# HDA-v1_1.net
KiCad netlist of a schematic drawn in EAGLE
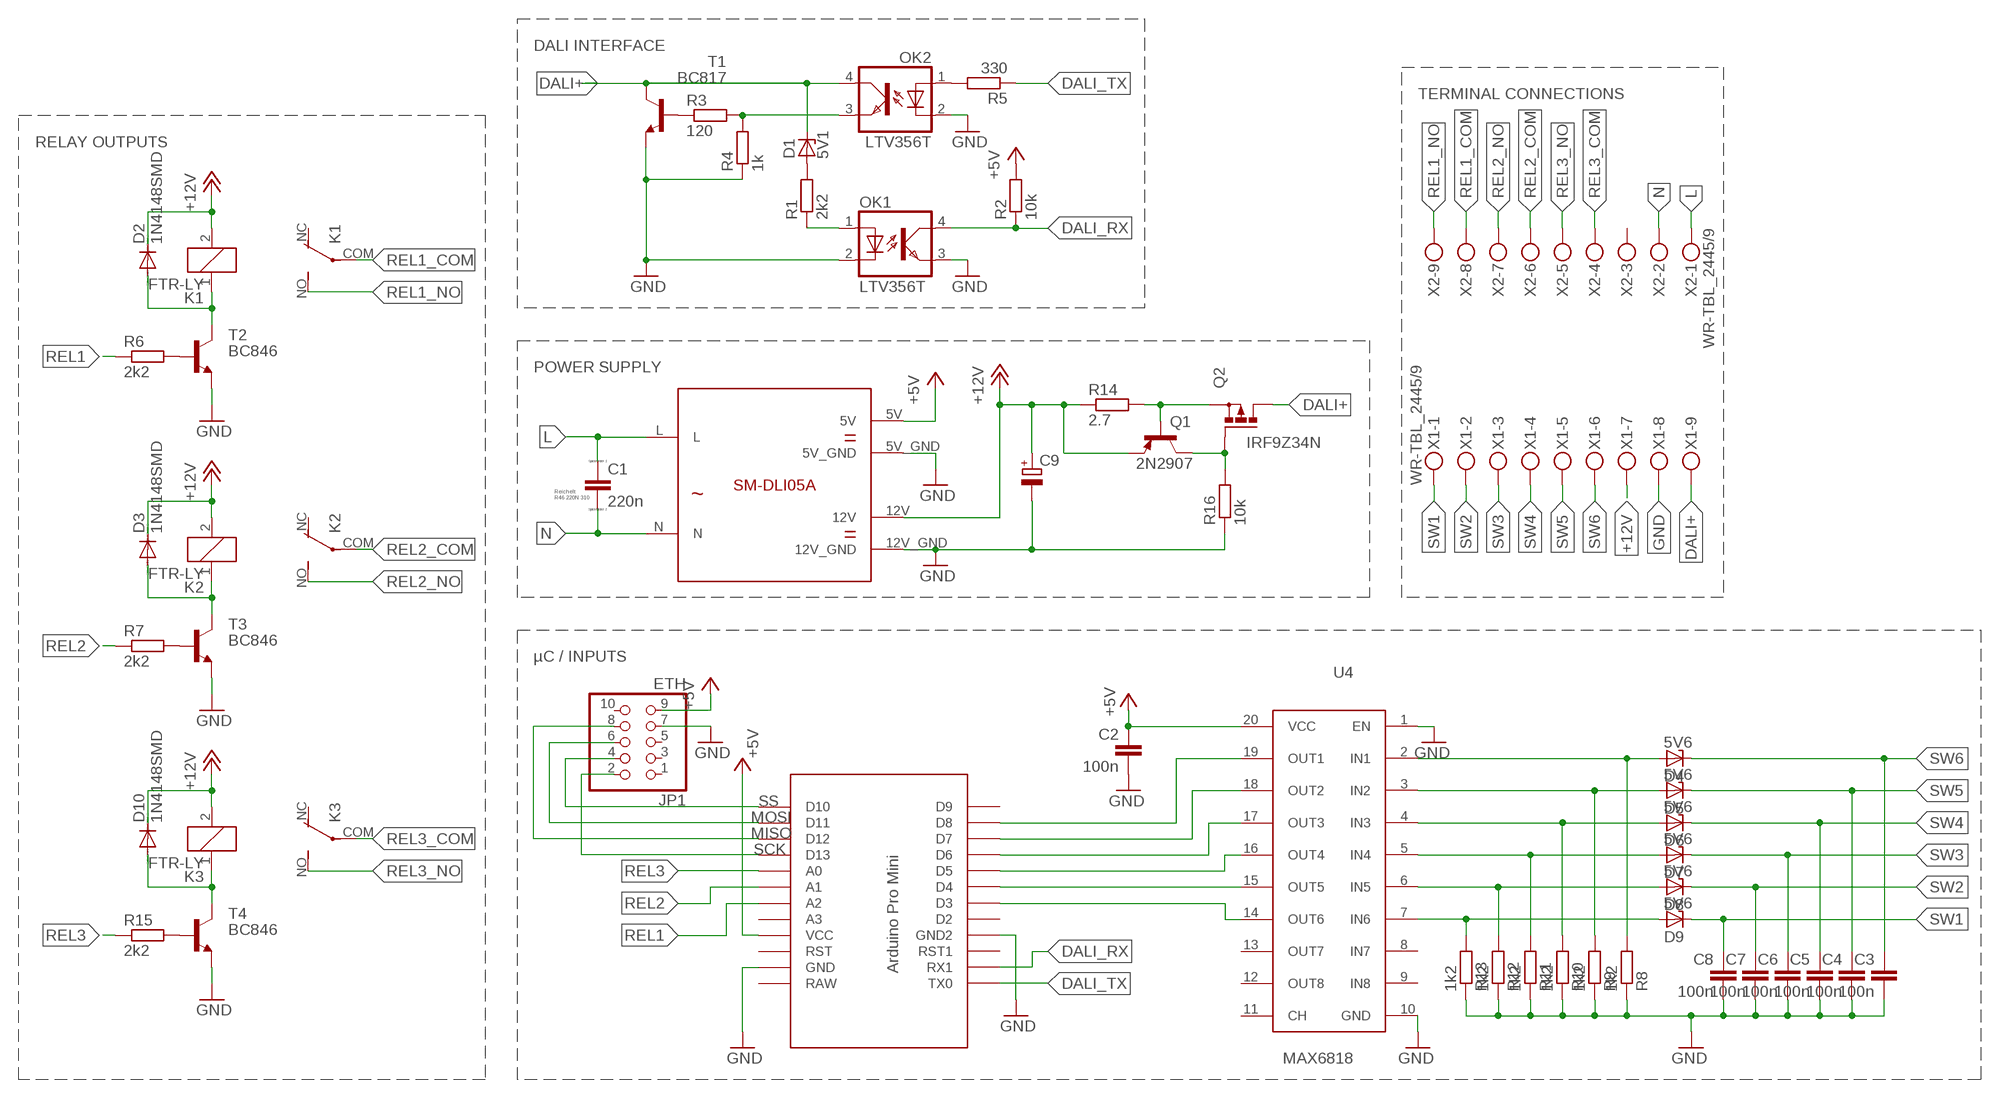
[diagram p0: schematic, sheet 1]

(export (version "E")
  (design (tool "Eeschema 10.0.6"))
  (components
    (comp (ref "C1")
      (value "220n")
      (footprint "eagle-import:ECQUAAF224")
      (libsource (lib "eagle-import") (part "X2_220N"))
    )
    (comp (ref "C2")
      (value "100n")
      (footprint "eagle-import:C1206K")
      (libsource (lib "eagle-import") (part "C-EUC1206K"))
    )
    (comp (ref "C3")
      (value "100n")
      (footprint "eagle-import:C1206K")
      (libsource (lib "eagle-import") (part "C-EUC1206K"))
    )
    (comp (ref "C4")
      (value "100n")
      (footprint "eagle-import:C1206K")
      (libsource (lib "eagle-import") (part "C-EUC1206K"))
    )
    (comp (ref "C5")
      (value "100n")
      (footprint "eagle-import:C1206K")
      (libsource (lib "eagle-import") (part "C-EUC1206K"))
    )
    (comp (ref "C6")
      (value "100n")
      (footprint "eagle-import:C1206K")
      (libsource (lib "eagle-import") (part "C-EUC1206K"))
    )
    (comp (ref "C7")
      (value "100n")
      (footprint "eagle-import:C1206K")
      (libsource (lib "eagle-import") (part "C-EUC1206K"))
    )
    (comp (ref "C8")
      (value "100n")
      (footprint "eagle-import:C1206K")
      (libsource (lib "eagle-import") (part "C-EUC1206K"))
    )
    (comp (ref "C9")
      (value "CPOL-EUSMCE")
      (footprint "eagle-import:SMC_E")
      (libsource (lib "eagle-import") (part "CPOL-EUSMCE"))
    )
    (comp (ref "D1")
      (value "5V1")
      (footprint "eagle-import:SOD80C")
      (libsource (lib "eagle-import") (part "ZENER-DIODESOD80C"))
    )
    (comp (ref "D2")
      (value "1N4148SMD")
      (footprint "eagle-import:SOD80C")
      (libsource (lib "eagle-import") (part "DIODE-SOD80C"))
    )
    (comp (ref "D3")
      (value "1N4148SMD")
      (footprint "eagle-import:SOD80C")
      (libsource (lib "eagle-import") (part "DIODE-SOD80C"))
    )
    (comp (ref "D4")
      (value "5V6")
      (footprint "eagle-import:SOD80C")
      (libsource (lib "eagle-import") (part "ZENER-DIODESOD80C"))
    )
    (comp (ref "D5")
      (value "5V6")
      (footprint "eagle-import:SOD80C")
      (libsource (lib "eagle-import") (part "ZENER-DIODESOD80C"))
    )
    (comp (ref "D6")
      (value "5V6")
      (footprint "eagle-import:SOD80C")
      (libsource (lib "eagle-import") (part "ZENER-DIODESOD80C"))
    )
    (comp (ref "D7")
      (value "5V6")
      (footprint "eagle-import:SOD80C")
      (libsource (lib "eagle-import") (part "ZENER-DIODESOD80C"))
    )
    (comp (ref "D8")
      (value "5V6")
      (footprint "eagle-import:SOD80C")
      (libsource (lib "eagle-import") (part "ZENER-DIODESOD80C"))
    )
    (comp (ref "D9")
      (value "5V6")
      (footprint "eagle-import:SOD80C")
      (libsource (lib "eagle-import") (part "ZENER-DIODESOD80C"))
    )
    (comp (ref "D10")
      (value "1N4148SMD")
      (footprint "eagle-import:SOD80C")
      (libsource (lib "eagle-import") (part "DIODE-SOD80C"))
    )
    (comp (ref "JP1")
      (value "ETH")
      (footprint "eagle-import:2X05")
      (libsource (lib "eagle-import") (part "PINHD-2X5"))
    )
    (comp (ref "K1")
      (value "FTR-LY")
      (footprint "eagle-import:PE-FORM-C")
      (fields (field (name "MPN") "APE3004H"))
      (libsource (lib "eagle-import") (part "PE30?04H"))
    )
    (comp (ref "K2")
      (value "FTR-LY")
      (footprint "eagle-import:PE-FORM-C")
      (fields (field (name "MPN") "APE3004H"))
      (libsource (lib "eagle-import") (part "PE30?04H"))
    )
    (comp (ref "K3")
      (value "FTR-LY")
      (footprint "eagle-import:PE-FORM-C")
      (fields (field (name "MPN") "APE3004H"))
      (libsource (lib "eagle-import") (part "PE30?04H"))
    )
    (comp (ref "OK1")
      (value "LTV356T")
      (footprint "eagle-import:SOP-4-2.54")
      (libsource (lib "eagle-import") (part "LTV356T"))
    )
    (comp (ref "OK2")
      (value "LTV356T")
      (footprint "eagle-import:SOP-4-2.54")
      (libsource (lib "eagle-import") (part "LTV356T"))
    )
    (comp (ref "Q1")
      (value "2N2907")
      (footprint "eagle-import:SOT23-BEC")
      (libsource (lib "eagle-import") (part "MMBT2907SMDALT1"))
    )
    (comp (ref "Q2")
      (value "IRF9Z34N")
      (footprint "eagle-import:TO220BV")
      (libsource (lib "eagle-import") (part "PMOSFET_PTO220BV"))
    )
    (comp (ref "R1")
      (value "2k2")
      (footprint "eagle-import:R1206")
      (libsource (lib "eagle-import") (part "R-EU_R1206"))
    )
    (comp (ref "R2")
      (value "10k")
      (footprint "eagle-import:R1206")
      (libsource (lib "eagle-import") (part "R-EU_R1206"))
    )
    (comp (ref "R3")
      (value "120")
      (footprint "eagle-import:R1206")
      (libsource (lib "eagle-import") (part "R-EU_R1206"))
    )
    (comp (ref "R4")
      (value "1k")
      (footprint "eagle-import:R1206")
      (libsource (lib "eagle-import") (part "R-EU_R1206"))
    )
    (comp (ref "R5")
      (value "330")
      (footprint "eagle-import:R1206")
      (libsource (lib "eagle-import") (part "R-EU_R1206"))
    )
    (comp (ref "R6")
      (value "2k2")
      (footprint "eagle-import:R1206")
      (libsource (lib "eagle-import") (part "R-EU_R1206"))
    )
    (comp (ref "R7")
      (value "2k2")
      (footprint "eagle-import:R1206")
      (libsource (lib "eagle-import") (part "R-EU_R1206"))
    )
    (comp (ref "R8")
      (value "1k2")
      (footprint "eagle-import:R1206")
      (libsource (lib "eagle-import") (part "R-EU_R1206"))
    )
    (comp (ref "R9")
      (value "1k2")
      (footprint "eagle-import:R1206")
      (libsource (lib "eagle-import") (part "R-EU_R1206"))
    )
    (comp (ref "R10")
      (value "1k2")
      (footprint "eagle-import:R1206")
      (libsource (lib "eagle-import") (part "R-EU_R1206"))
    )
    (comp (ref "R11")
      (value "1k2")
      (footprint "eagle-import:R1206")
      (libsource (lib "eagle-import") (part "R-EU_R1206"))
    )
    (comp (ref "R12")
      (value "1k2")
      (footprint "eagle-import:R1206")
      (libsource (lib "eagle-import") (part "R-EU_R1206"))
    )
    (comp (ref "R13")
      (value "1k2")
      (footprint "eagle-import:R1206")
      (libsource (lib "eagle-import") (part "R-EU_R1206"))
    )
    (comp (ref "R14")
      (value "2.7")
      (footprint "eagle-import:R1206")
      (libsource (lib "eagle-import") (part "R-EU_R1206"))
    )
    (comp (ref "R15")
      (value "2k2")
      (footprint "eagle-import:R1206")
      (libsource (lib "eagle-import") (part "R-EU_R1206"))
    )
    (comp (ref "R16")
      (value "10k")
      (footprint "eagle-import:R1206")
      (libsource (lib "eagle-import") (part "R-EU_R1206"))
    )
    (comp (ref "T1")
      (value "BC817")
      (footprint "eagle-import:SOT23-BEC")
      (libsource (lib "eagle-import") (part "BC817SMD-40"))
    )
    (comp (ref "T2")
      (value "BC846")
      (footprint "eagle-import:SOT23")
      (libsource (lib "eagle-import") (part "BC846"))
    )
    (comp (ref "T3")
      (value "BC846")
      (footprint "eagle-import:SOT23")
      (libsource (lib "eagle-import") (part "BC846"))
    )
    (comp (ref "T4")
      (value "BC846")
      (footprint "eagle-import:SOT23")
      (libsource (lib "eagle-import") (part "BC846"))
    )
    (comp (ref "U1")
      (value "SM-DLI05A")
      (footprint "eagle-import:SM-DLI05A")
      (libsource (lib "eagle-import") (part "SM-DLI05A"))
    )
    (comp (ref "U2")
      (value "ABK-PRO-MINI")
      (footprint "eagle-import:ABK-PRO-MINI")
      (libsource (lib "eagle-import") (part "ABK-PRO-MINI"))
    )
    (comp (ref "U4")
      (value "MAX6818")
      (footprint "eagle-import:SSOP20")
      (libsource (lib "eagle-import") (part "MAX6818"))
    )
    (comp (ref "X1")
      (value "WR-TBL_2445/9")
      (footprint "eagle-import:WR-TBL_2445_9")
      (libsource (lib "eagle-import") (part "WR-TBL_2445/9"))
    )
    (comp (ref "X2")
      (value "WR-TBL_2445/9")
      (footprint "eagle-import:WR-TBL_2445_9")
      (libsource (lib "eagle-import") (part "WR-TBL_2445/9"))
    )
  )
  (nets
    (net (code "1") (name "+5V") (class "Default")
      (node (ref "C2") (pin "1") (pinfunction "1_1") (pintype "passive"))
      (node (ref "JP1") (pin "9") (pinfunction "9_9") (pintype "passive"))
      (node (ref "R2") (pin "2") (pinfunction "2_2") (pintype "passive"))
      (node (ref "U1") (pin "5V") (pinfunction "5V_5V") (pintype "bidirectional"))
      (node (ref "U2") (pin "VCC") (pinfunction "VCC_VCC") (pintype "bidirectional"))
      (node (ref "U4") (pin "20") (pinfunction "VCC_20") (pintype "power_in"))
    )
    (net (code "2") (name "+12V") (class "Default")
      (node (ref "C9") (pin "+") (pinfunction "+_+") (pintype "passive"))
      (node (ref "D10") (pin "C") (pinfunction "C_C") (pintype "passive"))
      (node (ref "D2") (pin "C") (pinfunction "C_C") (pintype "passive"))
      (node (ref "D3") (pin "C") (pinfunction "C_C") (pintype "passive"))
      (node (ref "K1") (pin "2") (pinfunction "2_2") (pintype "passive"))
      (node (ref "K2") (pin "2") (pinfunction "2_2") (pintype "passive"))
      (node (ref "K3") (pin "2") (pinfunction "2_2") (pintype "passive"))
      (node (ref "Q1") (pin "E") (pinfunction "E_E") (pintype "passive"))
      (node (ref "R14") (pin "1") (pinfunction "1_1") (pintype "passive"))
      (node (ref "U1") (pin "12V") (pinfunction "12V_12V") (pintype "bidirectional"))
      (node (ref "X1") (pin "7") (pinfunction "KL_7") (pintype "passive"))
    )
    (net (code "3") (name "/MISO") (class "Default")
      (node (ref "JP1") (pin "8") (pinfunction "8_8") (pintype "passive"))
      (node (ref "U2") (pin "D12") (pinfunction "D12_D12") (pintype "bidirectional"))
    )
    (net (code "4") (name "/MOSI") (class "Default")
      (node (ref "JP1") (pin "6") (pinfunction "6_6") (pintype "passive"))
      (node (ref "U2") (pin "D11") (pinfunction "D11_D11") (pintype "bidirectional"))
    )
    (net (code "5") (name "/SCK") (class "Default")
      (node (ref "JP1") (pin "2") (pinfunction "2_2") (pintype "passive"))
      (node (ref "U2") (pin "D13") (pinfunction "D13_D13") (pintype "bidirectional"))
    )
    (net (code "6") (name "/SS") (class "Default")
      (node (ref "JP1") (pin "4") (pinfunction "4_4") (pintype "passive"))
      (node (ref "U2") (pin "D10") (pinfunction "D10_D10") (pintype "bidirectional"))
    )
    (net (code "7") (name "DALI+") (class "Default")
      (node (ref "D1") (pin "C") (pinfunction "C_C") (pintype "passive"))
      (node (ref "OK2") (pin "4") (pinfunction "COL_4") (pintype "passive"))
      (node (ref "Q2") (pin "D") (pinfunction "D_D") (pintype "passive"))
      (node (ref "T1") (pin "C") (pinfunction "C_C") (pintype "passive"))
      (node (ref "X1") (pin "9") (pinfunction "KL_9") (pintype "passive"))
    )
    (net (code "8") (name "DALI_RX") (class "Default")
      (node (ref "OK1") (pin "4") (pinfunction "COL_4") (pintype "passive"))
      (node (ref "R2") (pin "1") (pinfunction "1_1") (pintype "passive"))
      (node (ref "U2") (pin "RX1") (pinfunction "RX1_RX1") (pintype "bidirectional"))
    )
    (net (code "9") (name "DALI_TX") (class "Default")
      (node (ref "R5") (pin "1") (pinfunction "1_1") (pintype "passive"))
      (node (ref "U2") (pin "TX0") (pinfunction "TX0_TX0") (pintype "bidirectional"))
    )
    (net (code "10") (name "GND") (class "Default")
      (node (ref "C2") (pin "2") (pinfunction "2_2") (pintype "passive"))
      (node (ref "C3") (pin "2") (pinfunction "2_2") (pintype "passive"))
      (node (ref "C4") (pin "2") (pinfunction "2_2") (pintype "passive"))
      (node (ref "C5") (pin "2") (pinfunction "2_2") (pintype "passive"))
      (node (ref "C6") (pin "2") (pinfunction "2_2") (pintype "passive"))
      (node (ref "C7") (pin "2") (pinfunction "2_2") (pintype "passive"))
      (node (ref "C8") (pin "2") (pinfunction "2_2") (pintype "passive"))
      (node (ref "C9") (pin "-") (pinfunction "-_-") (pintype "passive"))
      (node (ref "JP1") (pin "7") (pinfunction "7_7") (pintype "passive"))
      (node (ref "OK1") (pin "2") (pinfunction "C_2") (pintype "passive"))
      (node (ref "OK1") (pin "3") (pinfunction "EMIT_3") (pintype "passive"))
      (node (ref "OK2") (pin "2") (pinfunction "C_2") (pintype "passive"))
      (node (ref "R10") (pin "1") (pinfunction "1_1") (pintype "passive"))
      (node (ref "R11") (pin "1") (pinfunction "1_1") (pintype "passive"))
      (node (ref "R12") (pin "1") (pinfunction "1_1") (pintype "passive"))
      (node (ref "R13") (pin "1") (pinfunction "1_1") (pintype "passive"))
      (node (ref "R16") (pin "1") (pinfunction "1_1") (pintype "passive"))
      (node (ref "R4") (pin "1") (pinfunction "1_1") (pintype "passive"))
      (node (ref "R8") (pin "1") (pinfunction "1_1") (pintype "passive"))
      (node (ref "R9") (pin "1") (pinfunction "1_1") (pintype "passive"))
      (node (ref "T1") (pin "E") (pinfunction "E_E") (pintype "passive"))
      (node (ref "T2") (pin "2") (pinfunction "E_2") (pintype "passive"))
      (node (ref "T3") (pin "2") (pinfunction "E_2") (pintype "passive"))
      (node (ref "T4") (pin "2") (pinfunction "E_2") (pintype "passive"))
      (node (ref "U1") (pin "12V_GND") (pinfunction "12V_GND_12V_GND") (pintype "bidirectional"))
      (node (ref "U1") (pin "5V_GND") (pinfunction "5V_GND_5V_GND") (pintype "bidirectional"))
      (node (ref "U2") (pin "GND") (pinfunction "GND_GND") (pintype "bidirectional"))
      (node (ref "U2") (pin "GND1") (pinfunction "GND2_GND1") (pintype "bidirectional"))
      (node (ref "U4") (pin "1") (pinfunction "EN_1") (pintype "bidirectional"))
      (node (ref "U4") (pin "10") (pinfunction "GND_10") (pintype "power_in"))
      (node (ref "X1") (pin "8") (pinfunction "KL_8") (pintype "passive"))
    )
    (net (code "11") (name "L") (class "Default")
      (node (ref "C1") (pin "1") (pinfunction "1_1") (pintype "passive"))
      (node (ref "U1") (pin "L") (pinfunction "L_L") (pintype "bidirectional"))
      (node (ref "X2") (pin "1") (pinfunction "KL_1") (pintype "passive"))
    )
    (net (code "12") (name "N") (class "Default")
      (node (ref "C1") (pin "2") (pinfunction "2_2") (pintype "passive"))
      (node (ref "U1") (pin "N") (pinfunction "N_N") (pintype "bidirectional"))
      (node (ref "X2") (pin "2") (pinfunction "KL_2") (pintype "passive"))
    )
    (net (code "13") (name "Net-(D1-PadA)") (class "Default")
      (node (ref "D1") (pin "A") (pinfunction "A_A") (pintype "passive"))
      (node (ref "R1") (pin "2") (pinfunction "2_2") (pintype "passive"))
    )
    (net (code "14") (name "Net-(OK1-A)") (class "Default")
      (node (ref "OK1") (pin "1") (pinfunction "A_1") (pintype "passive"))
      (node (ref "R1") (pin "1") (pinfunction "1_1") (pintype "passive"))
    )
    (net (code "15") (name "Net-(OK2-A)") (class "Default")
      (node (ref "OK2") (pin "1") (pinfunction "A_1") (pintype "passive"))
      (node (ref "R5") (pin "2") (pinfunction "2_2") (pintype "passive"))
    )
    (net (code "16") (name "Net-(OK2-EMIT)") (class "Default")
      (node (ref "OK2") (pin "3") (pinfunction "EMIT_3") (pintype "passive"))
      (node (ref "R3") (pin "2") (pinfunction "2_2") (pintype "passive"))
      (node (ref "R4") (pin "2") (pinfunction "2_2") (pintype "passive"))
    )
    (net (code "17") (name "Net-(Q1-PadB)") (class "Default")
      (node (ref "Q1") (pin "B") (pinfunction "B_B") (pintype "passive"))
      (node (ref "Q2") (pin "S") (pinfunction "S_S") (pintype "passive"))
      (node (ref "R14") (pin "2") (pinfunction "2_2") (pintype "passive"))
    )
    (net (code "18") (name "Net-(Q1-PadC)") (class "Default")
      (node (ref "Q1") (pin "C") (pinfunction "C_C") (pintype "passive"))
      (node (ref "Q2") (pin "G") (pinfunction "G_G") (pintype "passive"))
      (node (ref "R16") (pin "2") (pinfunction "2_2") (pintype "passive"))
    )
    (net (code "19") (name "Net-(R3-Pad1)") (class "Default")
      (node (ref "R3") (pin "1") (pinfunction "1_1") (pintype "passive"))
      (node (ref "T1") (pin "B") (pinfunction "B_B") (pintype "passive"))
    )
    (net (code "20") (name "Net-(T2-B)") (class "Default")
      (node (ref "R6") (pin "2") (pinfunction "2_2") (pintype "passive"))
      (node (ref "T2") (pin "1") (pinfunction "B_1") (pintype "passive"))
    )
    (net (code "21") (name "Net-(T2-C)") (class "Default")
      (node (ref "D2") (pin "A") (pinfunction "A_A") (pintype "passive"))
      (node (ref "K1") (pin "1") (pinfunction "1_1") (pintype "passive"))
      (node (ref "T2") (pin "3") (pinfunction "C_3") (pintype "passive"))
    )
    (net (code "22") (name "Net-(T3-B)") (class "Default")
      (node (ref "R7") (pin "2") (pinfunction "2_2") (pintype "passive"))
      (node (ref "T3") (pin "1") (pinfunction "B_1") (pintype "passive"))
    )
    (net (code "23") (name "Net-(T3-C)") (class "Default")
      (node (ref "D3") (pin "A") (pinfunction "A_A") (pintype "passive"))
      (node (ref "K2") (pin "1") (pinfunction "1_1") (pintype "passive"))
      (node (ref "T3") (pin "3") (pinfunction "C_3") (pintype "passive"))
    )
    (net (code "24") (name "Net-(T4-B)") (class "Default")
      (node (ref "R15") (pin "2") (pinfunction "2_2") (pintype "passive"))
      (node (ref "T4") (pin "1") (pinfunction "B_1") (pintype "passive"))
    )
    (net (code "25") (name "Net-(T4-C)") (class "Default")
      (node (ref "D10") (pin "A") (pinfunction "A_A") (pintype "passive"))
      (node (ref "K3") (pin "1") (pinfunction "1_1") (pintype "passive"))
      (node (ref "T4") (pin "3") (pinfunction "C_3") (pintype "passive"))
    )
    (net (code "26") (name "Net-(U4-IN1)") (class "Default")
      (node (ref "D4") (pin "A") (pinfunction "A_A") (pintype "passive"))
      (node (ref "R8") (pin "2") (pinfunction "2_2") (pintype "passive"))
      (node (ref "U4") (pin "2") (pinfunction "IN1_2") (pintype "bidirectional"))
    )
    (net (code "27") (name "Net-(U4-IN2)") (class "Default")
      (node (ref "D5") (pin "A") (pinfunction "A_A") (pintype "passive"))
      (node (ref "R9") (pin "2") (pinfunction "2_2") (pintype "passive"))
      (node (ref "U4") (pin "3") (pinfunction "IN2_3") (pintype "bidirectional"))
    )
    (net (code "28") (name "Net-(U4-IN3)") (class "Default")
      (node (ref "D6") (pin "A") (pinfunction "A_A") (pintype "passive"))
      (node (ref "R10") (pin "2") (pinfunction "2_2") (pintype "passive"))
      (node (ref "U4") (pin "4") (pinfunction "IN3_4") (pintype "bidirectional"))
    )
    (net (code "29") (name "Net-(U4-IN4)") (class "Default")
      (node (ref "D7") (pin "A") (pinfunction "A_A") (pintype "passive"))
      (node (ref "R11") (pin "2") (pinfunction "2_2") (pintype "passive"))
      (node (ref "U4") (pin "5") (pinfunction "IN4_5") (pintype "bidirectional"))
    )
    (net (code "30") (name "Net-(U4-IN5)") (class "Default")
      (node (ref "D8") (pin "A") (pinfunction "A_A") (pintype "passive"))
      (node (ref "R12") (pin "2") (pinfunction "2_2") (pintype "passive"))
      (node (ref "U4") (pin "6") (pinfunction "IN5_6") (pintype "bidirectional"))
    )
    (net (code "31") (name "Net-(U4-IN6)") (class "Default")
      (node (ref "D9") (pin "A") (pinfunction "A_A") (pintype "passive"))
      (node (ref "R13") (pin "2") (pinfunction "2_2") (pintype "passive"))
      (node (ref "U4") (pin "7") (pinfunction "IN6_7") (pintype "bidirectional"))
    )
    (net (code "32") (name "Net-(U4-OUT1)") (class "Default")
      (node (ref "U2") (pin "D8") (pinfunction "D8_D8") (pintype "bidirectional"))
      (node (ref "U4") (pin "19") (pinfunction "OUT1_19") (pintype "bidirectional"))
    )
    (net (code "33") (name "Net-(U4-OUT2)") (class "Default")
      (node (ref "U2") (pin "D7") (pinfunction "D7_D7") (pintype "bidirectional"))
      (node (ref "U4") (pin "18") (pinfunction "OUT2_18") (pintype "bidirectional"))
    )
    (net (code "34") (name "Net-(U4-OUT3)") (class "Default")
      (node (ref "U2") (pin "D6") (pinfunction "D6_D6") (pintype "bidirectional"))
      (node (ref "U4") (pin "17") (pinfunction "OUT3_17") (pintype "bidirectional"))
    )
    (net (code "35") (name "Net-(U4-OUT4)") (class "Default")
      (node (ref "U2") (pin "D5") (pinfunction "D5_D5") (pintype "bidirectional"))
      (node (ref "U4") (pin "16") (pinfunction "OUT4_16") (pintype "bidirectional"))
    )
    (net (code "36") (name "Net-(U4-OUT5)") (class "Default")
      (node (ref "U2") (pin "D4") (pinfunction "D4_D4") (pintype "bidirectional"))
      (node (ref "U4") (pin "15") (pinfunction "OUT5_15") (pintype "bidirectional"))
    )
    (net (code "37") (name "Net-(U4-OUT6)") (class "Default")
      (node (ref "U2") (pin "D3") (pinfunction "D3_D3") (pintype "bidirectional"))
      (node (ref "U4") (pin "14") (pinfunction "OUT6_14") (pintype "bidirectional"))
    )
    (net (code "38") (name "REL1") (class "Default")
      (node (ref "R6") (pin "1") (pinfunction "1_1") (pintype "passive"))
      (node (ref "U2") (pin "A2") (pinfunction "A2_A2") (pintype "bidirectional"))
    )
    (net (code "39") (name "REL1_COM") (class "Default")
      (node (ref "K1") (pin "COM") (pinfunction "P_COM") (pintype "passive"))
      (node (ref "X2") (pin "8") (pinfunction "KL_8") (pintype "passive"))
    )
    (net (code "40") (name "REL1_NO") (class "Default")
      (node (ref "K1") (pin "NO") (pinfunction "S_NO") (pintype "passive"))
      (node (ref "X2") (pin "9") (pinfunction "KL_9") (pintype "passive"))
    )
    (net (code "41") (name "REL2") (class "Default")
      (node (ref "R7") (pin "1") (pinfunction "1_1") (pintype "passive"))
      (node (ref "U2") (pin "A1") (pinfunction "A1_A1") (pintype "bidirectional"))
    )
    (net (code "42") (name "REL2_COM") (class "Default")
      (node (ref "K2") (pin "COM") (pinfunction "P_COM") (pintype "passive"))
      (node (ref "X2") (pin "6") (pinfunction "KL_6") (pintype "passive"))
    )
    (net (code "43") (name "REL2_NO") (class "Default")
      (node (ref "K2") (pin "NO") (pinfunction "S_NO") (pintype "passive"))
      (node (ref "X2") (pin "7") (pinfunction "KL_7") (pintype "passive"))
    )
    (net (code "44") (name "REL3") (class "Default")
      (node (ref "R15") (pin "1") (pinfunction "1_1") (pintype "passive"))
      (node (ref "U2") (pin "A0") (pinfunction "A0_A0") (pintype "bidirectional"))
    )
    (net (code "45") (name "REL3_COM") (class "Default")
      (node (ref "K3") (pin "COM") (pinfunction "P_COM") (pintype "passive"))
      (node (ref "X2") (pin "4") (pinfunction "KL_4") (pintype "passive"))
    )
    (net (code "46") (name "REL3_NO") (class "Default")
      (node (ref "K3") (pin "NO") (pinfunction "S_NO") (pintype "passive"))
      (node (ref "X2") (pin "5") (pinfunction "KL_5") (pintype "passive"))
    )
    (net (code "47") (name "SW1") (class "Default")
      (node (ref "C8") (pin "1") (pinfunction "1_1") (pintype "passive"))
      (node (ref "D9") (pin "C") (pinfunction "C_C") (pintype "passive"))
      (node (ref "X1") (pin "1") (pinfunction "KL_1") (pintype "passive"))
    )
    (net (code "48") (name "SW2") (class "Default")
      (node (ref "C7") (pin "1") (pinfunction "1_1") (pintype "passive"))
      (node (ref "D8") (pin "C") (pinfunction "C_C") (pintype "passive"))
      (node (ref "X1") (pin "2") (pinfunction "KL_2") (pintype "passive"))
    )
    (net (code "49") (name "SW3") (class "Default")
      (node (ref "C6") (pin "1") (pinfunction "1_1") (pintype "passive"))
      (node (ref "D7") (pin "C") (pinfunction "C_C") (pintype "passive"))
      (node (ref "X1") (pin "3") (pinfunction "KL_3") (pintype "passive"))
    )
    (net (code "50") (name "SW4") (class "Default")
      (node (ref "C5") (pin "1") (pinfunction "1_1") (pintype "passive"))
      (node (ref "D6") (pin "C") (pinfunction "C_C") (pintype "passive"))
      (node (ref "X1") (pin "4") (pinfunction "KL_4") (pintype "passive"))
    )
    (net (code "51") (name "SW5") (class "Default")
      (node (ref "C4") (pin "1") (pinfunction "1_1") (pintype "passive"))
      (node (ref "D5") (pin "C") (pinfunction "C_C") (pintype "passive"))
      (node (ref "X1") (pin "5") (pinfunction "KL_5") (pintype "passive"))
    )
    (net (code "52") (name "SW6") (class "Default")
      (node (ref "C3") (pin "1") (pinfunction "1_1") (pintype "passive"))
      (node (ref "D4") (pin "C") (pinfunction "C_C") (pintype "passive"))
      (node (ref "X1") (pin "6") (pinfunction "KL_6") (pintype "passive"))
    )
    (net (code "53") (name "unconnected-(JP1-Pad1)") (class "Default")
      (node (ref "JP1") (pin "1") (pinfunction "1_1") (pintype "passive"))
    )
    (net (code "54") (name "unconnected-(JP1-Pad3)") (class "Default")
      (node (ref "JP1") (pin "3") (pinfunction "3_3") (pintype "passive"))
    )
    (net (code "55") (name "unconnected-(JP1-Pad5)") (class "Default")
      (node (ref "JP1") (pin "5") (pinfunction "5_5") (pintype "passive"))
    )
    (net (code "56") (name "unconnected-(JP1-Pad10)") (class "Default")
      (node (ref "JP1") (pin "10") (pinfunction "10_10") (pintype "passive"))
    )
    (net (code "57") (name "unconnected-(K1B-O-PadNC)") (class "Default")
      (node (ref "K1") (pin "NC") (pinfunction "O_NC") (pintype "passive"))
    )
    (net (code "58") (name "unconnected-(K2B-O-PadNC)") (class "Default")
      (node (ref "K2") (pin "NC") (pinfunction "O_NC") (pintype "passive"))
    )
    (net (code "59") (name "unconnected-(K3B-O-PadNC)") (class "Default")
      (node (ref "K3") (pin "NC") (pinfunction "O_NC") (pintype "passive"))
    )
    (net (code "60") (name "unconnected-(U2-PadA3)") (class "Default")
      (node (ref "U2") (pin "A3") (pinfunction "A3_A3") (pintype "bidirectional"))
    )
    (net (code "61") (name "unconnected-(U2-PadD2)") (class "Default")
      (node (ref "U2") (pin "D2") (pinfunction "D2_D2") (pintype "bidirectional"))
    )
    (net (code "62") (name "unconnected-(U2-PadD9)") (class "Default")
      (node (ref "U2") (pin "D9") (pinfunction "D9_D9") (pintype "bidirectional"))
    )
    (net (code "63") (name "unconnected-(U2-PadRAW)") (class "Default")
      (node (ref "U2") (pin "RAW") (pinfunction "RAW_RAW") (pintype "bidirectional"))
    )
    (net (code "64") (name "unconnected-(U2-PadRST)") (class "Default")
      (node (ref "U2") (pin "RST") (pinfunction "RST_RST") (pintype "bidirectional"))
    )
    (net (code "65") (name "unconnected-(U2-PadRST1)") (class "Default")
      (node (ref "U2") (pin "RST1") (pinfunction "RST1_RST1") (pintype "bidirectional"))
    )
    (net (code "66") (name "unconnected-(U4-CH-Pad11)") (class "Default")
      (node (ref "U4") (pin "11") (pinfunction "CH_11") (pintype "bidirectional"))
    )
    (net (code "67") (name "unconnected-(U4-IN7-Pad8)") (class "Default")
      (node (ref "U4") (pin "8") (pinfunction "IN7_8") (pintype "bidirectional"))
    )
    (net (code "68") (name "unconnected-(U4-IN8-Pad9)") (class "Default")
      (node (ref "U4") (pin "9") (pinfunction "IN8_9") (pintype "bidirectional"))
    )
    (net (code "69") (name "unconnected-(U4-OUT7-Pad13)") (class "Default")
      (node (ref "U4") (pin "13") (pinfunction "OUT7_13") (pintype "bidirectional"))
    )
    (net (code "70") (name "unconnected-(U4-OUT8-Pad12)") (class "Default")
      (node (ref "U4") (pin "12") (pinfunction "OUT8_12") (pintype "bidirectional"))
    )
    (net (code "71") (name "unconnected-(X2C-KL-Pad3)") (class "Default")
      (node (ref "X2") (pin "3") (pinfunction "KL_3") (pintype "passive"))
    )
  )
)
